# CNC-Controller.net
KiCad netlist of a schematic drawn in EAGLE
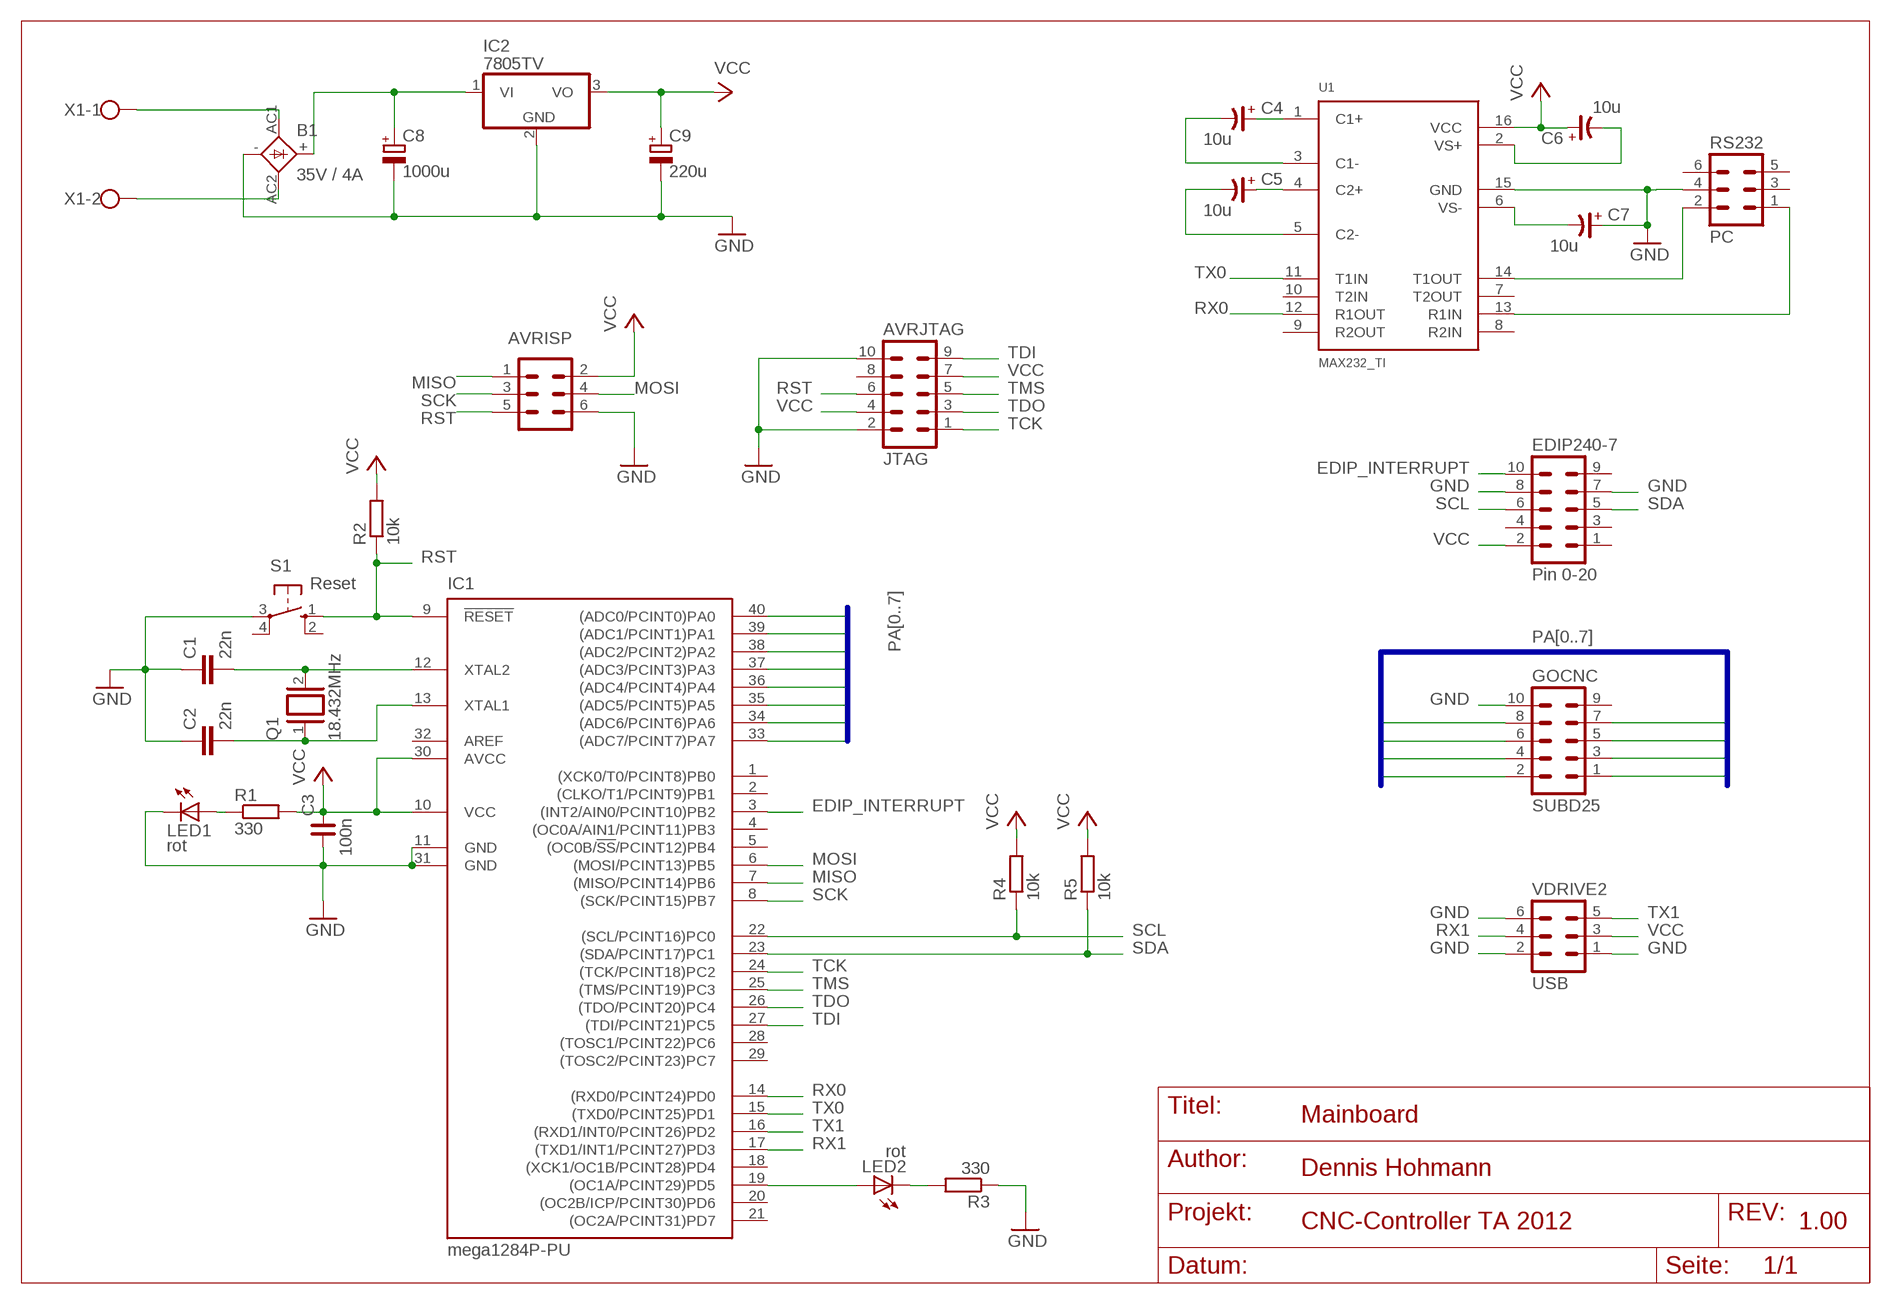
[diagram p0: schematic, sheet 1]

(export (version "E")
  (design (tool "Eeschema 10.0.6"))
  (components
    (comp (ref "AVRISP")
      (value "ISP")
      (footprint "eagle-import:ML6")
      (libsource (lib "eagle-import") (part "ML6"))
    )
    (comp (ref "AVRJTAG")
      (value "JTAG")
      (footprint "eagle-import:ML10")
      (libsource (lib "eagle-import") (part "ML10"))
    )
    (comp (ref "B1")
      (value "35V / 4A")
      (footprint "eagle-import:KBU")
      (libsource (lib "eagle-import") (part "KBU"))
    )
    (comp (ref "C1")
      (value "22n")
      (footprint "eagle-import:C025-025X050")
      (libsource (lib "eagle-import") (part "C-EU025-025X050"))
    )
    (comp (ref "C2")
      (value "22n")
      (footprint "eagle-import:C025-025X050")
      (libsource (lib "eagle-import") (part "C-EU025-025X050"))
    )
    (comp (ref "C3")
      (value "100n")
      (footprint "eagle-import:C025-050X025")
      (libsource (lib "eagle-import") (part "C_C025-050X025"))
    )
    (comp (ref "C4")
      (value "10u")
      (footprint "eagle-import:CTT-025-050")
      (libsource (lib "eagle-import") (part "CP_TT025-050"))
    )
    (comp (ref "C5")
      (value "10u")
      (footprint "eagle-import:CTT-025-050")
      (libsource (lib "eagle-import") (part "CP_TT025-050"))
    )
    (comp (ref "C6")
      (value "10u")
      (footprint "eagle-import:CTT-025-050")
      (libsource (lib "eagle-import") (part "CP_TT025-050"))
    )
    (comp (ref "C7")
      (value "10u")
      (footprint "eagle-import:CTT-025-050")
      (libsource (lib "eagle-import") (part "CP_TT025-050"))
    )
    (comp (ref "C8")
      (value "1000u")
      (footprint "eagle-import:E5-13")
      (libsource (lib "eagle-import") (part "CPOL-EUE5-13"))
    )
    (comp (ref "C9")
      (value "220u")
      (footprint "eagle-import:E2-5")
      (libsource (lib "eagle-import") (part "CPOL-EUE2-5"))
    )
    (comp (ref "EDIP240-7")
      (value "Pin 0-20")
      (footprint "eagle-import:ML10")
      (libsource (lib "eagle-import") (part "ML10"))
    )
    (comp (ref "GOCNC")
      (value "SUBD25")
      (footprint "eagle-import:ML10")
      (libsource (lib "eagle-import") (part "ML10"))
    )
    (comp (ref "IC1")
      (value "mega1284P-PU")
      (footprint "eagle-import:DIL40")
      (libsource (lib "eagle-import") (part "MEGA164P/324P/644P-PU"))
    )
    (comp (ref "IC2")
      (value "7805TV")
      (footprint "eagle-import:TO220V")
      (libsource (lib "eagle-import") (part "78TV05"))
    )
    (comp (ref "LED1")
      (value "rot")
      (footprint "eagle-import:LED3MM")
      (libsource (lib "eagle-import") (part "LED3MM"))
    )
    (comp (ref "LED2")
      (value "rot")
      (footprint "eagle-import:LED3MM")
      (libsource (lib "eagle-import") (part "LED3MM"))
    )
    (comp (ref "Q1")
      (value "18.432MHz")
      (footprint "eagle-import:QS")
      (libsource (lib "eagle-import") (part "XTAL/S"))
    )
    (comp (ref "R1")
      (value "330")
      (footprint "eagle-import:0207_10")
      (libsource (lib "eagle-import") (part "R-EU_0207/10"))
    )
    (comp (ref "R2")
      (value "10k")
      (footprint "eagle-import:0207_10")
      (libsource (lib "eagle-import") (part "R-EU_0207/10"))
    )
    (comp (ref "R3")
      (value "330")
      (footprint "eagle-import:0207_10")
      (libsource (lib "eagle-import") (part "R-EU_0207/10"))
    )
    (comp (ref "R4")
      (value "10k")
      (footprint "eagle-import:0207_10")
      (libsource (lib "eagle-import") (part "R-EU_0207/10"))
    )
    (comp (ref "R5")
      (value "10k")
      (footprint "eagle-import:0207_10")
      (libsource (lib "eagle-import") (part "R-EU_0207/10"))
    )
    (comp (ref "RS232")
      (value "PC")
      (footprint "eagle-import:ML6")
      (libsource (lib "eagle-import") (part "ML6"))
    )
    (comp (ref "S1")
      (value "Reset")
      (footprint "eagle-import:B3F-10XX")
      (libsource (lib "eagle-import") (part "10-XX"))
    )
    (comp (ref "U1")
      (value "MAX232_TI")
      (footprint "eagle-import:DIL16")
      (libsource (lib "eagle-import") (part "MAX232_TI"))
    )
    (comp (ref "VDRIVE2")
      (value "USB")
      (footprint "eagle-import:ML6")
      (libsource (lib "eagle-import") (part "ML6"))
    )
    (comp (ref "X1")
      (value "W237-102")
      (footprint "eagle-import:W237-102")
      (fields (field (name "MPN") "237-102"))
      (libsource (lib "eagle-import") (part "W237-102"))
    )
  )
  (nets
    (net (code "1") (name "/AREF") (class "Default")
      (node (ref "IC1") (pin "32") (pinfunction "AREF_32") (pintype "power_in"))
    )
    (net (code "2") (name "/EDIP_INTERRUPT") (class "Default")
      (node (ref "EDIP240-7") (pin "10") (pinfunction "10_10") (pintype "passive"))
      (node (ref "IC1") (pin "3") (pinfunction "(INT2/AIN0/PCINT10)PB2_3") (pintype "bidirectional"))
    )
    (net (code "3") (name "/MISO") (class "Default")
      (node (ref "AVRISP") (pin "1") (pinfunction "1_1") (pintype "passive"))
      (node (ref "IC1") (pin "7") (pinfunction "(MISO/PCINT14)PB6_7") (pintype "bidirectional"))
    )
    (net (code "4") (name "/MOSI") (class "Default")
      (node (ref "AVRISP") (pin "4") (pinfunction "4_4") (pintype "passive"))
      (node (ref "IC1") (pin "6") (pinfunction "(MOSI/PCINT13)PB5_6") (pintype "bidirectional"))
    )
    (net (code "5") (name "/PA0") (class "Default")
      (node (ref "GOCNC") (pin "1") (pinfunction "1_1") (pintype "passive"))
      (node (ref "IC1") (pin "40") (pinfunction "(ADC0/PCINT0)PA0_40") (pintype "bidirectional"))
    )
    (net (code "6") (name "/PA1") (class "Default")
      (node (ref "GOCNC") (pin "2") (pinfunction "2_2") (pintype "passive"))
      (node (ref "IC1") (pin "39") (pinfunction "(ADC1/PCINT1)PA1_39") (pintype "bidirectional"))
    )
    (net (code "7") (name "/PA2") (class "Default")
      (node (ref "GOCNC") (pin "3") (pinfunction "3_3") (pintype "passive"))
      (node (ref "IC1") (pin "38") (pinfunction "(ADC2/PCINT2)PA2_38") (pintype "bidirectional"))
    )
    (net (code "8") (name "/PA3") (class "Default")
      (node (ref "GOCNC") (pin "4") (pinfunction "4_4") (pintype "passive"))
      (node (ref "IC1") (pin "37") (pinfunction "(ADC3/PCINT3)PA3_37") (pintype "bidirectional"))
    )
    (net (code "9") (name "/PA4") (class "Default")
      (node (ref "GOCNC") (pin "5") (pinfunction "5_5") (pintype "passive"))
      (node (ref "IC1") (pin "36") (pinfunction "(ADC4/PCINT4)PA4_36") (pintype "bidirectional"))
    )
    (net (code "10") (name "/PA5") (class "Default")
      (node (ref "GOCNC") (pin "6") (pinfunction "6_6") (pintype "passive"))
      (node (ref "IC1") (pin "35") (pinfunction "(ADC5/PCINT5)PA5_35") (pintype "bidirectional"))
    )
    (net (code "11") (name "/PA6") (class "Default")
      (node (ref "GOCNC") (pin "7") (pinfunction "7_7") (pintype "passive"))
      (node (ref "IC1") (pin "34") (pinfunction "(ADC6/PCINT6)PA6_34") (pintype "bidirectional"))
    )
    (net (code "12") (name "/PA7") (class "Default")
      (node (ref "GOCNC") (pin "8") (pinfunction "8_8") (pintype "passive"))
      (node (ref "IC1") (pin "33") (pinfunction "(ADC7/PCINT7)PA7_33") (pintype "bidirectional"))
    )
    (net (code "14") (name "/RST") (class "Default")
      (node (ref "AVRISP") (pin "5") (pinfunction "5_5") (pintype "passive"))
      (node (ref "AVRJTAG") (pin "6") (pinfunction "6_6") (pintype "passive"))
      (node (ref "IC1") (pin "9") (pinfunction "~{RESET}_9") (pintype "input"))
      (node (ref "R2") (pin "1") (pinfunction "1_1") (pintype "passive"))
      (node (ref "S1") (pin "1") (pinfunction "S_1") (pintype "passive"))
    )
    (net (code "15") (name "/RX0") (class "Default")
      (node (ref "IC1") (pin "14") (pinfunction "(RXD0/PCINT24)PD0_14") (pintype "bidirectional"))
      (node (ref "U1") (pin "12") (pinfunction "R1OUT_12") (pintype "bidirectional"))
    )
    (net (code "16") (name "/RX1") (class "Default")
      (node (ref "IC1") (pin "17") (pinfunction "(TXD1/INT1/PCINT27)PD3_17") (pintype "bidirectional"))
      (node (ref "VDRIVE2") (pin "4") (pinfunction "4_4") (pintype "passive"))
    )
    (net (code "17") (name "/SCK") (class "Default")
      (node (ref "AVRISP") (pin "3") (pinfunction "3_3") (pintype "passive"))
      (node (ref "IC1") (pin "8") (pinfunction "(SCK/PCINT15)PB7_8") (pintype "bidirectional"))
    )
    (net (code "18") (name "/SCL") (class "Default")
      (node (ref "EDIP240-7") (pin "6") (pinfunction "6_6") (pintype "passive"))
      (node (ref "IC1") (pin "22") (pinfunction "(SCL/PCINT16)PC0_22") (pintype "bidirectional"))
      (node (ref "R4") (pin "1") (pinfunction "1_1") (pintype "passive"))
    )
    (net (code "19") (name "/SDA") (class "Default")
      (node (ref "EDIP240-7") (pin "5") (pinfunction "5_5") (pintype "passive"))
      (node (ref "IC1") (pin "23") (pinfunction "(SDA/PCINT17)PC1_23") (pintype "bidirectional"))
      (node (ref "R5") (pin "1") (pinfunction "1_1") (pintype "passive"))
    )
    (net (code "20") (name "/TCK") (class "Default")
      (node (ref "AVRJTAG") (pin "1") (pinfunction "1_1") (pintype "passive"))
      (node (ref "IC1") (pin "24") (pinfunction "(TCK/PCINT18)PC2_24") (pintype "bidirectional"))
    )
    (net (code "21") (name "/TDI") (class "Default")
      (node (ref "AVRJTAG") (pin "9") (pinfunction "9_9") (pintype "passive"))
      (node (ref "IC1") (pin "27") (pinfunction "(TDI/PCINT21)PC5_27") (pintype "bidirectional"))
    )
    (net (code "22") (name "/TDO") (class "Default")
      (node (ref "AVRJTAG") (pin "3") (pinfunction "3_3") (pintype "passive"))
      (node (ref "IC1") (pin "26") (pinfunction "(TDO/PCINT20)PC4_26") (pintype "bidirectional"))
    )
    (net (code "23") (name "/TMS") (class "Default")
      (node (ref "AVRJTAG") (pin "5") (pinfunction "5_5") (pintype "passive"))
      (node (ref "IC1") (pin "25") (pinfunction "(TMS/PCINT19)PC3_25") (pintype "bidirectional"))
    )
    (net (code "24") (name "/TX0") (class "Default")
      (node (ref "IC1") (pin "15") (pinfunction "(TXD0/PCINT25)PD1_15") (pintype "bidirectional"))
      (node (ref "U1") (pin "11") (pinfunction "T1IN_11") (pintype "bidirectional"))
    )
    (net (code "25") (name "/TX1") (class "Default")
      (node (ref "IC1") (pin "16") (pinfunction "(RXD1/INT0/PCINT26)PD2_16") (pintype "bidirectional"))
      (node (ref "VDRIVE2") (pin "5") (pinfunction "5_5") (pintype "passive"))
    )
    (net (code "26") (name "GND") (class "Default")
      (node (ref "AVRISP") (pin "6") (pinfunction "6_6") (pintype "passive"))
      (node (ref "AVRJTAG") (pin "10") (pinfunction "10_10") (pintype "passive"))
      (node (ref "AVRJTAG") (pin "2") (pinfunction "2_2") (pintype "passive"))
      (node (ref "B1") (pin "-") (pinfunction "-_-") (pintype "passive"))
      (node (ref "C1") (pin "1") (pinfunction "1_1") (pintype "passive"))
      (node (ref "C2") (pin "1") (pinfunction "1_1") (pintype "passive"))
      (node (ref "C3") (pin "1") (pinfunction "1_1") (pintype "passive"))
      (node (ref "C7") (pin "+") (pinfunction "+_+") (pintype "passive"))
      (node (ref "C8") (pin "-") (pinfunction "-_-") (pintype "passive"))
      (node (ref "C9") (pin "-") (pinfunction "-_-") (pintype "passive"))
      (node (ref "EDIP240-7") (pin "7") (pinfunction "7_7") (pintype "passive"))
      (node (ref "EDIP240-7") (pin "8") (pinfunction "8_8") (pintype "passive"))
      (node (ref "GOCNC") (pin "10") (pinfunction "10_10") (pintype "passive"))
      (node (ref "IC1") (pin "11") (pinfunction "GND_11") (pintype "power_in"))
      (node (ref "IC1") (pin "31") (pinfunction "GND_31") (pintype "power_in"))
      (node (ref "IC2") (pin "2") (pinfunction "GND_2") (pintype "passive"))
      (node (ref "LED1") (pin "K") (pinfunction "C_K") (pintype "passive"))
      (node (ref "R3") (pin "1") (pinfunction "1_1") (pintype "passive"))
      (node (ref "RS232") (pin "4") (pinfunction "4_4") (pintype "passive"))
      (node (ref "S1") (pin "3") (pinfunction "P_3") (pintype "passive"))
      (node (ref "U1") (pin "15") (pinfunction "GND_15") (pintype "bidirectional"))
      (node (ref "VDRIVE2") (pin "1") (pinfunction "1_1") (pintype "passive"))
      (node (ref "VDRIVE2") (pin "2") (pinfunction "2_2") (pintype "passive"))
      (node (ref "VDRIVE2") (pin "6") (pinfunction "6_6") (pintype "passive"))
    )
    (net (code "27") (name "Net-(IC1-(OC1A{slash}PCINT29)PD5)") (class "Default")
      (node (ref "IC1") (pin "19") (pinfunction "(OC1A/PCINT29)PD5_19") (pintype "bidirectional"))
      (node (ref "LED2") (pin "A") (pinfunction "A_A") (pintype "passive"))
    )
    (net (code "28") (name "Net-(IC1-XTAL1)") (class "Default")
      (node (ref "C2") (pin "2") (pinfunction "2_2") (pintype "passive"))
      (node (ref "IC1") (pin "13") (pinfunction "XTAL1_13") (pintype "input"))
      (node (ref "Q1") (pin "1") (pinfunction "1_1") (pintype "passive"))
    )
    (net (code "29") (name "Net-(IC1-XTAL2)") (class "Default")
      (node (ref "C1") (pin "2") (pinfunction "2_2") (pintype "passive"))
      (node (ref "IC1") (pin "12") (pinfunction "XTAL2_12") (pintype "output"))
      (node (ref "Q1") (pin "2") (pinfunction "2_2") (pintype "passive"))
    )
    (net (code "30") (name "Net-(IC2-VI)") (class "Default")
      (node (ref "B1") (pin "+") (pinfunction "+_+") (pintype "passive"))
      (node (ref "C8") (pin "+") (pinfunction "+_+") (pintype "passive"))
      (node (ref "IC2") (pin "1") (pinfunction "VI_1") (pintype "input"))
    )
    (net (code "31") (name "Net-(LED1-PadA)") (class "Default")
      (node (ref "LED1") (pin "A") (pinfunction "A_A") (pintype "passive"))
      (node (ref "R1") (pin "1") (pinfunction "1_1") (pintype "passive"))
    )
    (net (code "32") (name "Net-(LED2-C)") (class "Default")
      (node (ref "LED2") (pin "K") (pinfunction "C_K") (pintype "passive"))
      (node (ref "R3") (pin "2") (pinfunction "2_2") (pintype "passive"))
    )
    (net (code "33") (name "Net-(U1-C1+)") (class "Default")
      (node (ref "C4") (pin "+") (pinfunction "+_+") (pintype "passive"))
      (node (ref "U1") (pin "1") (pinfunction "C1+_1") (pintype "bidirectional"))
    )
    (net (code "34") (name "Net-(U1-C1-)") (class "Default")
      (node (ref "C4") (pin "-") (pinfunction "-_-") (pintype "passive"))
      (node (ref "U1") (pin "3") (pinfunction "C1-_3") (pintype "bidirectional"))
    )
    (net (code "35") (name "Net-(U1-C2+)") (class "Default")
      (node (ref "C5") (pin "+") (pinfunction "+_+") (pintype "passive"))
      (node (ref "U1") (pin "4") (pinfunction "C2+_4") (pintype "bidirectional"))
    )
    (net (code "36") (name "Net-(U1-C2-)") (class "Default")
      (node (ref "C5") (pin "-") (pinfunction "-_-") (pintype "passive"))
      (node (ref "U1") (pin "5") (pinfunction "C2-_5") (pintype "bidirectional"))
    )
    (net (code "37") (name "Net-(U1-R1IN)") (class "Default")
      (node (ref "RS232") (pin "1") (pinfunction "1_1") (pintype "passive"))
      (node (ref "U1") (pin "13") (pinfunction "R1IN_13") (pintype "bidirectional"))
    )
    (net (code "38") (name "Net-(U1-T1OUT)") (class "Default")
      (node (ref "RS232") (pin "2") (pinfunction "2_2") (pintype "passive"))
      (node (ref "U1") (pin "14") (pinfunction "T1OUT_14") (pintype "bidirectional"))
    )
    (net (code "39") (name "Net-(U1-VS+)") (class "Default")
      (node (ref "C6") (pin "-") (pinfunction "-_-") (pintype "passive"))
      (node (ref "U1") (pin "2") (pinfunction "VS+_2") (pintype "bidirectional"))
    )
    (net (code "40") (name "Net-(U1-VS-)") (class "Default")
      (node (ref "C7") (pin "-") (pinfunction "-_-") (pintype "passive"))
      (node (ref "U1") (pin "6") (pinfunction "VS-_6") (pintype "bidirectional"))
    )
    (net (code "41") (name "Net-(X1A-KL)") (class "Default")
      (node (ref "B1") (pin "AC1") (pinfunction "AC1_AC1") (pintype "passive"))
      (node (ref "X1") (pin "1") (pinfunction "KL_1") (pintype "passive"))
    )
    (net (code "42") (name "Net-(X1B-KL)") (class "Default")
      (node (ref "B1") (pin "AC2") (pinfunction "AC2_AC2") (pintype "passive"))
      (node (ref "X1") (pin "2") (pinfunction "KL_2") (pintype "passive"))
    )
    (net (code "43") (name "VCC") (class "Default")
      (node (ref "AVRISP") (pin "2") (pinfunction "2_2") (pintype "passive"))
      (node (ref "AVRJTAG") (pin "4") (pinfunction "4_4") (pintype "passive"))
      (node (ref "AVRJTAG") (pin "7") (pinfunction "7_7") (pintype "passive"))
      (node (ref "C3") (pin "2") (pinfunction "2_2") (pintype "passive"))
      (node (ref "C6") (pin "+") (pinfunction "+_+") (pintype "passive"))
      (node (ref "C9") (pin "+") (pinfunction "+_+") (pintype "passive"))
      (node (ref "EDIP240-7") (pin "2") (pinfunction "2_2") (pintype "passive"))
      (node (ref "IC1") (pin "10") (pinfunction "VCC_10") (pintype "power_in"))
      (node (ref "IC1") (pin "30") (pinfunction "AVCC_30") (pintype "power_in"))
      (node (ref "IC2") (pin "3") (pinfunction "VO_3") (pintype "passive"))
      (node (ref "R1") (pin "2") (pinfunction "2_2") (pintype "passive"))
      (node (ref "R2") (pin "2") (pinfunction "2_2") (pintype "passive"))
      (node (ref "R4") (pin "2") (pinfunction "2_2") (pintype "passive"))
      (node (ref "R5") (pin "2") (pinfunction "2_2") (pintype "passive"))
      (node (ref "U1") (pin "16") (pinfunction "VCC_16") (pintype "bidirectional"))
      (node (ref "VDRIVE2") (pin "3") (pinfunction "3_3") (pintype "passive"))
    )
    (net (code "44") (name "unconnected-(AVRJTAG-Pad8)") (class "Default")
      (node (ref "AVRJTAG") (pin "8") (pinfunction "8_8") (pintype "passive"))
    )
    (net (code "45") (name "unconnected-(EDIP240-7-Pad1)") (class "Default")
      (node (ref "EDIP240-7") (pin "1") (pinfunction "1_1") (pintype "passive"))
    )
    (net (code "46") (name "unconnected-(EDIP240-7-Pad3)") (class "Default")
      (node (ref "EDIP240-7") (pin "3") (pinfunction "3_3") (pintype "passive"))
    )
    (net (code "47") (name "unconnected-(EDIP240-7-Pad4)") (class "Default")
      (node (ref "EDIP240-7") (pin "4") (pinfunction "4_4") (pintype "passive"))
    )
    (net (code "48") (name "unconnected-(EDIP240-7-Pad9)") (class "Default")
      (node (ref "EDIP240-7") (pin "9") (pinfunction "9_9") (pintype "passive"))
    )
    (net (code "49") (name "unconnected-(GOCNC-Pad9)") (class "Default")
      (node (ref "GOCNC") (pin "9") (pinfunction "9_9") (pintype "passive"))
    )
    (net (code "50") (name "unconnected-(IC1-(CLKO{slash}T1{slash}PCINT9)PB1-Pad2)") (class "Default")
      (node (ref "IC1") (pin "2") (pinfunction "(CLKO/T1/PCINT9)PB1_2") (pintype "bidirectional"))
    )
    (net (code "51") (name "unconnected-(IC1-(OC0A{slash}AIN1{slash}PCINT11)PB3-Pad4)") (class "Default")
      (node (ref "IC1") (pin "4") (pinfunction "(OC0A/AIN1/PCINT11)PB3_4") (pintype "bidirectional"))
    )
    (net (code "52") (name "unconnected-(IC1-(OC0B{slash}~{SS}{slash}PCINT12)PB4-Pad5)") (class "Default")
      (node (ref "IC1") (pin "5") (pinfunction "(OC0B/~{SS}/PCINT12)PB4_5") (pintype "bidirectional"))
    )
    (net (code "53") (name "unconnected-(IC1-(OC2A{slash}PCINT31)PD7-Pad21)") (class "Default")
      (node (ref "IC1") (pin "21") (pinfunction "(OC2A/PCINT31)PD7_21") (pintype "bidirectional"))
    )
    (net (code "54") (name "unconnected-(IC1-(OC2B{slash}ICP{slash}PCINT30)PD6-Pad20)") (class "Default")
      (node (ref "IC1") (pin "20") (pinfunction "(OC2B/ICP/PCINT30)PD6_20") (pintype "bidirectional"))
    )
    (net (code "55") (name "unconnected-(IC1-(TOSC1{slash}PCINT22)PC6-Pad28)") (class "Default")
      (node (ref "IC1") (pin "28") (pinfunction "(TOSC1/PCINT22)PC6_28") (pintype "bidirectional"))
    )
    (net (code "56") (name "unconnected-(IC1-(TOSC2{slash}PCINT23)PC7-Pad29)") (class "Default")
      (node (ref "IC1") (pin "29") (pinfunction "(TOSC2/PCINT23)PC7_29") (pintype "bidirectional"))
    )
    (net (code "57") (name "unconnected-(IC1-(XCK0{slash}T0{slash}PCINT8)PB0-Pad1)") (class "Default")
      (node (ref "IC1") (pin "1") (pinfunction "(XCK0/T0/PCINT8)PB0_1") (pintype "bidirectional"))
    )
    (net (code "58") (name "unconnected-(IC1-(XCK1{slash}OC1B{slash}PCINT28)PD4-Pad18)") (class "Default")
      (node (ref "IC1") (pin "18") (pinfunction "(XCK1/OC1B/PCINT28)PD4_18") (pintype "bidirectional"))
    )
    (net (code "59") (name "unconnected-(RS232-Pad3)") (class "Default")
      (node (ref "RS232") (pin "3") (pinfunction "3_3") (pintype "passive"))
    )
    (net (code "60") (name "unconnected-(RS232-Pad5)") (class "Default")
      (node (ref "RS232") (pin "5") (pinfunction "5_5") (pintype "passive"))
    )
    (net (code "61") (name "unconnected-(RS232-Pad6)") (class "Default")
      (node (ref "RS232") (pin "6") (pinfunction "6_6") (pintype "passive"))
    )
    (net (code "62") (name "unconnected-(S1-P1-Pad4)") (class "Default")
      (node (ref "S1") (pin "4") (pinfunction "P1_4") (pintype "passive"))
    )
    (net (code "63") (name "unconnected-(S1-S1-Pad2)") (class "Default")
      (node (ref "S1") (pin "2") (pinfunction "S1_2") (pintype "passive"))
    )
    (net (code "64") (name "unconnected-(U1-R2IN-Pad8)") (class "Default")
      (node (ref "U1") (pin "8") (pinfunction "R2IN_8") (pintype "bidirectional"))
    )
    (net (code "65") (name "unconnected-(U1-R2OUT-Pad9)") (class "Default")
      (node (ref "U1") (pin "9") (pinfunction "R2OUT_9") (pintype "bidirectional"))
    )
    (net (code "66") (name "unconnected-(U1-T2IN-Pad10)") (class "Default")
      (node (ref "U1") (pin "10") (pinfunction "T2IN_10") (pintype "bidirectional"))
    )
    (net (code "67") (name "unconnected-(U1-T2OUT-Pad7)") (class "Default")
      (node (ref "U1") (pin "7") (pinfunction "T2OUT_7") (pintype "bidirectional"))
    )
  )
)
